# PCB1_new.net
KiCad netlist of a schematic drawn in EAGLE
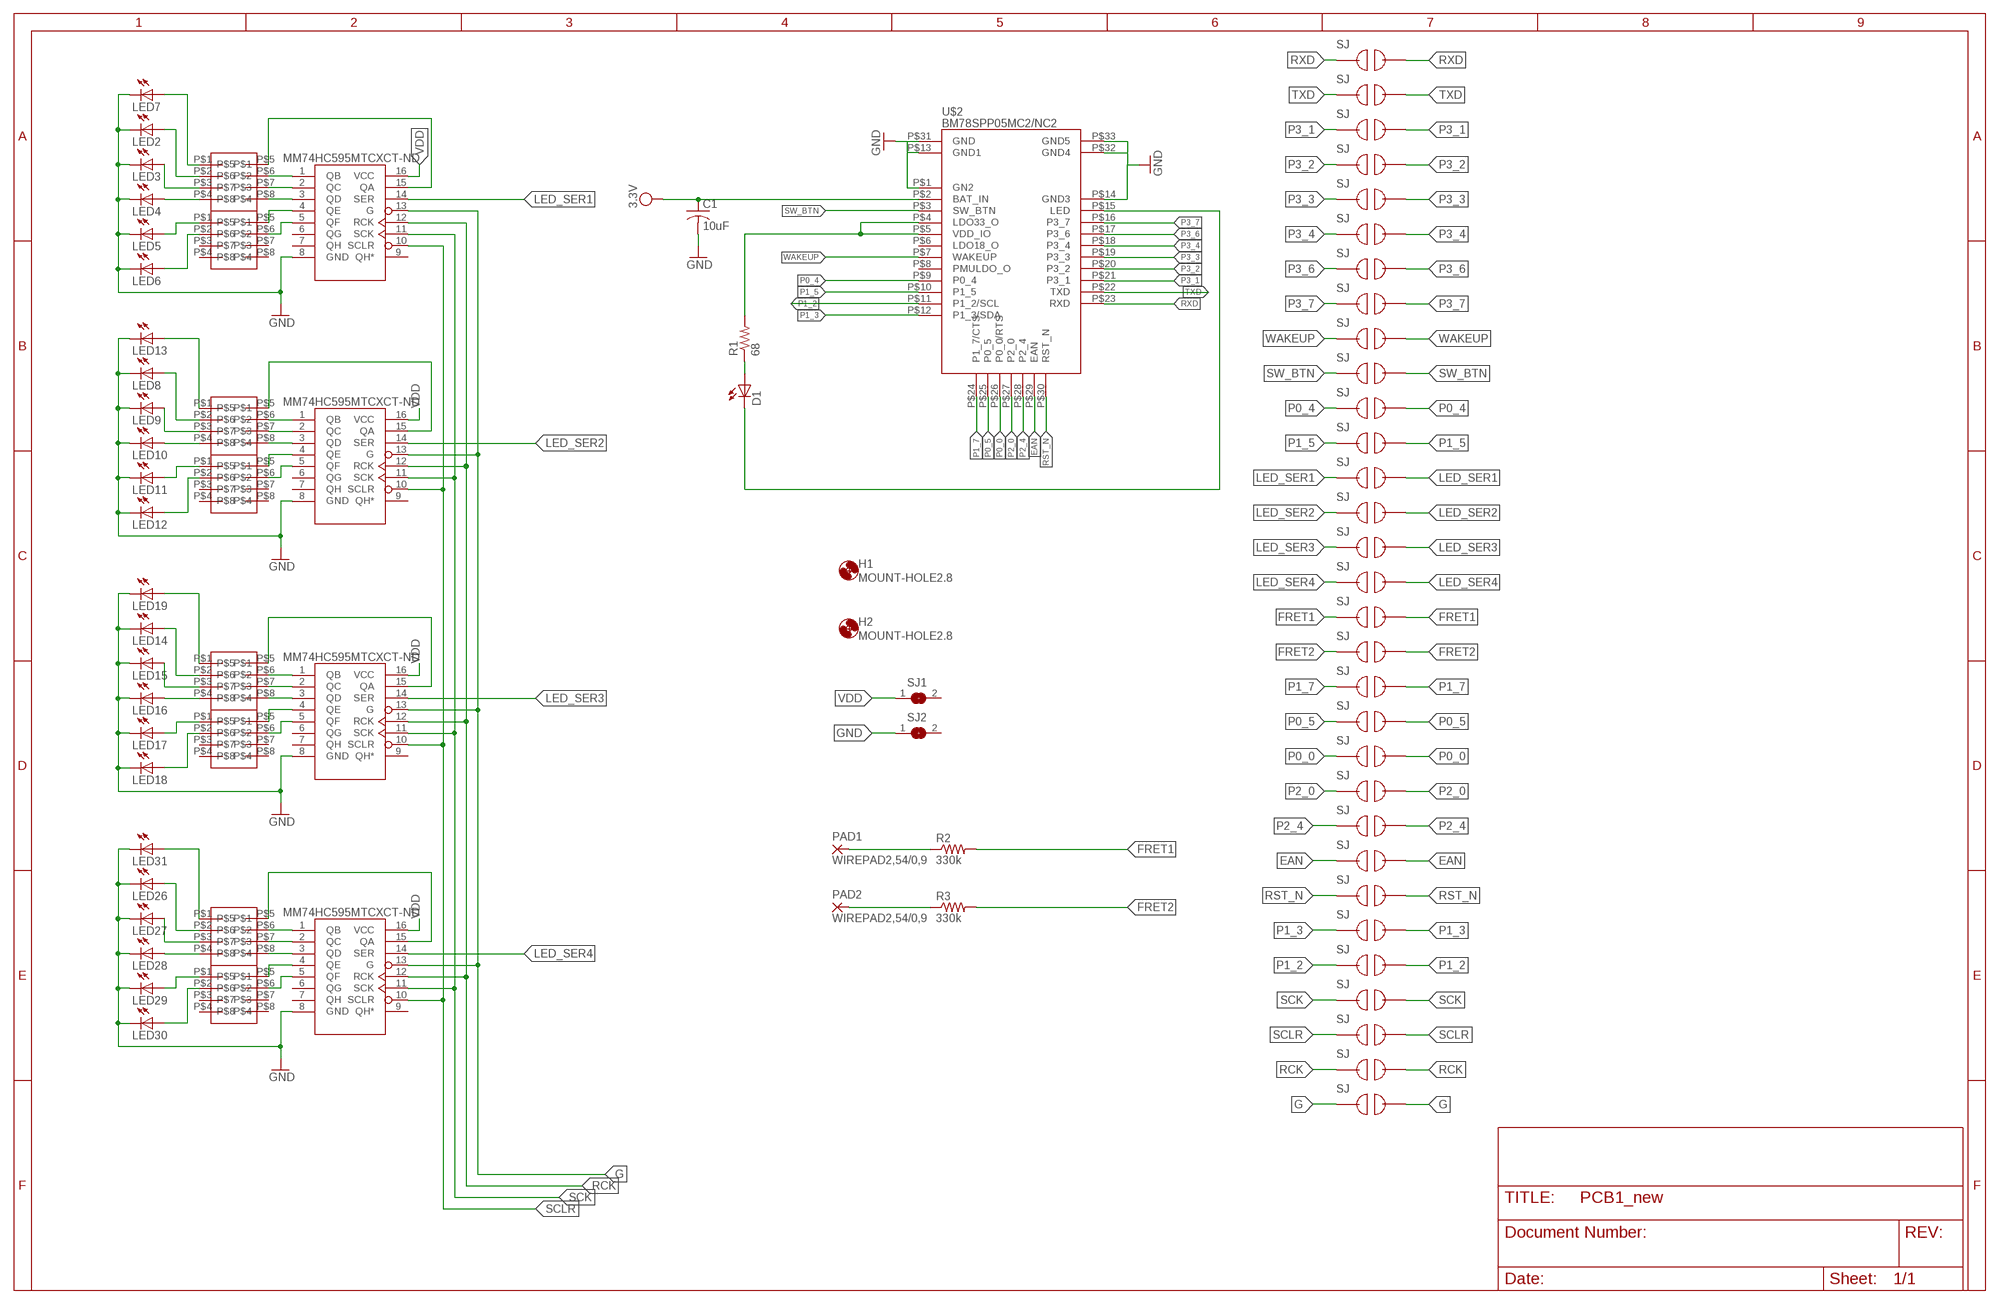
[diagram p0: schematic, sheet 1]

(export (version "E")
  (design (tool "Eeschema 10.0.6"))
  (components
    (comp (ref "C1")
      (value "10uF")
      (footprint "eagle-import:C0805")
      (libsource (lib "eagle-import") (part "C-USC0805"))
    )
    (comp (ref "D1")
      (value "LEDSMT1206")
      (footprint "eagle-import:1206")
      (libsource (lib "eagle-import") (part "LEDSMT1206"))
    )
    (comp (ref "H1")
      (value "MOUNT-HOLE2.8")
      (footprint "eagle-import:2,8")
      (libsource (lib "eagle-import") (part "MOUNT-HOLE2.8"))
    )
    (comp (ref "H2")
      (value "MOUNT-HOLE2.8")
      (footprint "eagle-import:2,8")
      (libsource (lib "eagle-import") (part "MOUNT-HOLE2.8"))
    )
    (comp (ref "LED2")
      (value "LEDSMT1206")
      (footprint "eagle-import:1206")
      (libsource (lib "eagle-import") (part "LEDSMT1206"))
    )
    (comp (ref "LED3")
      (value "LEDSMT1206")
      (footprint "eagle-import:1206")
      (libsource (lib "eagle-import") (part "LEDSMT1206"))
    )
    (comp (ref "LED4")
      (value "LEDSMT1206")
      (footprint "eagle-import:1206")
      (libsource (lib "eagle-import") (part "LEDSMT1206"))
    )
    (comp (ref "LED5")
      (value "LEDSMT1206")
      (footprint "eagle-import:1206")
      (libsource (lib "eagle-import") (part "LEDSMT1206"))
    )
    (comp (ref "LED6")
      (value "LEDSMT1206")
      (footprint "eagle-import:1206")
      (libsource (lib "eagle-import") (part "LEDSMT1206"))
    )
    (comp (ref "LED7")
      (value "LEDSMT1206")
      (footprint "eagle-import:1206")
      (libsource (lib "eagle-import") (part "LEDSMT1206"))
    )
    (comp (ref "LED8")
      (value "LEDSMT1206")
      (footprint "eagle-import:1206")
      (libsource (lib "eagle-import") (part "LEDSMT1206"))
    )
    (comp (ref "LED9")
      (value "LEDSMT1206")
      (footprint "eagle-import:1206")
      (libsource (lib "eagle-import") (part "LEDSMT1206"))
    )
    (comp (ref "LED10")
      (value "LEDSMT1206")
      (footprint "eagle-import:1206")
      (libsource (lib "eagle-import") (part "LEDSMT1206"))
    )
    (comp (ref "LED11")
      (value "LEDSMT1206")
      (footprint "eagle-import:1206")
      (libsource (lib "eagle-import") (part "LEDSMT1206"))
    )
    (comp (ref "LED12")
      (value "LEDSMT1206")
      (footprint "eagle-import:1206")
      (libsource (lib "eagle-import") (part "LEDSMT1206"))
    )
    (comp (ref "LED13")
      (value "LEDSMT1206")
      (footprint "eagle-import:1206")
      (libsource (lib "eagle-import") (part "LEDSMT1206"))
    )
    (comp (ref "LED14")
      (value "LEDSMT1206")
      (footprint "eagle-import:1206")
      (libsource (lib "eagle-import") (part "LEDSMT1206"))
    )
    (comp (ref "LED15")
      (value "LEDSMT1206")
      (footprint "eagle-import:1206")
      (libsource (lib "eagle-import") (part "LEDSMT1206"))
    )
    (comp (ref "LED16")
      (value "LEDSMT1206")
      (footprint "eagle-import:1206")
      (libsource (lib "eagle-import") (part "LEDSMT1206"))
    )
    (comp (ref "LED17")
      (value "LEDSMT1206")
      (footprint "eagle-import:1206")
      (libsource (lib "eagle-import") (part "LEDSMT1206"))
    )
    (comp (ref "LED18")
      (value "LEDSMT1206")
      (footprint "eagle-import:1206")
      (libsource (lib "eagle-import") (part "LEDSMT1206"))
    )
    (comp (ref "LED19")
      (value "LEDSMT1206")
      (footprint "eagle-import:1206")
      (libsource (lib "eagle-import") (part "LEDSMT1206"))
    )
    (comp (ref "LED26")
      (value "LEDSMT1206")
      (footprint "eagle-import:1206")
      (libsource (lib "eagle-import") (part "LEDSMT1206"))
    )
    (comp (ref "LED27")
      (value "LEDSMT1206")
      (footprint "eagle-import:1206")
      (libsource (lib "eagle-import") (part "LEDSMT1206"))
    )
    (comp (ref "LED28")
      (value "LEDSMT1206")
      (footprint "eagle-import:1206")
      (libsource (lib "eagle-import") (part "LEDSMT1206"))
    )
    (comp (ref "LED29")
      (value "LEDSMT1206")
      (footprint "eagle-import:1206")
      (libsource (lib "eagle-import") (part "LEDSMT1206"))
    )
    (comp (ref "LED30")
      (value "LEDSMT1206")
      (footprint "eagle-import:1206")
      (libsource (lib "eagle-import") (part "LEDSMT1206"))
    )
    (comp (ref "LED31")
      (value "LEDSMT1206")
      (footprint "eagle-import:1206")
      (libsource (lib "eagle-import") (part "LEDSMT1206"))
    )
    (comp (ref "PAD1")
      (value "WIREPAD2,54/0,9")
      (footprint "eagle-import:2,54_0,9")
      (libsource (lib "eagle-import") (part "WIREPAD2,54/0,9"))
    )
    (comp (ref "PAD2")
      (value "WIREPAD2,54/0,9")
      (footprint "eagle-import:2,54_0,9")
      (libsource (lib "eagle-import") (part "WIREPAD2,54/0,9"))
    )
    (comp (ref "R1")
      (value "68")
      (footprint "eagle-import:M0805")
      (libsource (lib "eagle-import") (part "R-US_M0805"))
    )
    (comp (ref "R2")
      (value "330k")
      (footprint "eagle-import:R0805")
      (libsource (lib "eagle-import") (part "R-US_R0805"))
    )
    (comp (ref "R3")
      (value "330k")
      (footprint "eagle-import:R0805")
      (libsource (lib "eagle-import") (part "R-US_R0805"))
    )
    (comp (ref "RN1")
      (value "MNR04MRAPJ680")
      (footprint "eagle-import:MNR04")
      (libsource (lib "eagle-import") (part "MNR04MRAPJ680"))
    )
    (comp (ref "RN2")
      (value "MNR04MRAPJ680")
      (footprint "eagle-import:MNR04")
      (libsource (lib "eagle-import") (part "MNR04MRAPJ680"))
    )
    (comp (ref "SJ1")
      (value "SJW")
      (footprint "eagle-import:SJW")
      (libsource (lib "eagle-import") (part "SJW"))
    )
    (comp (ref "SJ2")
      (value "SJW")
      (footprint "eagle-import:SJW")
      (libsource (lib "eagle-import") (part "SJW"))
    )
    (comp (ref "U$1")
      (value "MM74HC595TSSOP-LD16")
      (footprint "eagle-import:MM74HC595MTCXCT-ND")
      (libsource (lib "eagle-import") (part "MM74HC595TSSOP-LD16"))
    )
    (comp (ref "U$2")
      (value "BM78SPP05MC2/NC2")
      (footprint "eagle-import:BM78SPP05MC2_NC2")
      (libsource (lib "eagle-import") (part "BM78SPP05MC2/NC2"))
    )
    (comp (ref "U$3")
      (value "MM74HC595TSSOP-LD16")
      (footprint "eagle-import:MM74HC595MTCXCT-ND")
      (libsource (lib "eagle-import") (part "MM74HC595TSSOP-LD16"))
    )
    (comp (ref "U$4")
      (value "MM74HC595TSSOP-LD16")
      (footprint "eagle-import:MM74HC595MTCXCT-ND")
      (libsource (lib "eagle-import") (part "MM74HC595TSSOP-LD16"))
    )
    (comp (ref "U$5")
      (value "MM74HC595TSSOP-LD16")
      (footprint "eagle-import:MM74HC595MTCXCT-ND")
      (libsource (lib "eagle-import") (part "MM74HC595TSSOP-LD16"))
    )
    (comp (ref "U$6")
      (value "JUMPER")
      (footprint "eagle-import:JUMPER")
      (libsource (lib "eagle-import") (part "JUMPER"))
    )
    (comp (ref "U$7")
      (value "JUMPER")
      (footprint "eagle-import:JUMPER")
      (libsource (lib "eagle-import") (part "JUMPER"))
    )
    (comp (ref "U$8")
      (value "JUMPER")
      (footprint "eagle-import:JUMPER")
      (libsource (lib "eagle-import") (part "JUMPER"))
    )
    (comp (ref "U$9")
      (value "JUMPER")
      (footprint "eagle-import:JUMPER")
      (libsource (lib "eagle-import") (part "JUMPER"))
    )
    (comp (ref "U$10")
      (value "JUMPER")
      (footprint "eagle-import:JUMPER")
      (libsource (lib "eagle-import") (part "JUMPER"))
    )
    (comp (ref "U$11")
      (value "JUMPER")
      (footprint "eagle-import:JUMPER")
      (libsource (lib "eagle-import") (part "JUMPER"))
    )
    (comp (ref "U$12")
      (value "JUMPER")
      (footprint "eagle-import:JUMPER")
      (libsource (lib "eagle-import") (part "JUMPER"))
    )
    (comp (ref "U$13")
      (value "JUMPER")
      (footprint "eagle-import:JUMPER")
      (libsource (lib "eagle-import") (part "JUMPER"))
    )
    (comp (ref "U$14")
      (value "JUMPER")
      (footprint "eagle-import:JUMPER")
      (libsource (lib "eagle-import") (part "JUMPER"))
    )
    (comp (ref "U$15")
      (value "JUMPER")
      (footprint "eagle-import:JUMPER")
      (libsource (lib "eagle-import") (part "JUMPER"))
    )
    (comp (ref "U$16")
      (value "JUMPER")
      (footprint "eagle-import:JUMPER")
      (libsource (lib "eagle-import") (part "JUMPER"))
    )
    (comp (ref "U$17")
      (value "JUMPER")
      (footprint "eagle-import:JUMPER")
      (libsource (lib "eagle-import") (part "JUMPER"))
    )
    (comp (ref "U$18")
      (value "JUMPER")
      (footprint "eagle-import:JUMPER")
      (libsource (lib "eagle-import") (part "JUMPER"))
    )
    (comp (ref "U$19")
      (value "JUMPER")
      (footprint "eagle-import:JUMPER")
      (libsource (lib "eagle-import") (part "JUMPER"))
    )
    (comp (ref "U$20")
      (value "JUMPER")
      (footprint "eagle-import:JUMPER")
      (libsource (lib "eagle-import") (part "JUMPER"))
    )
    (comp (ref "U$21")
      (value "JUMPER")
      (footprint "eagle-import:JUMPER")
      (libsource (lib "eagle-import") (part "JUMPER"))
    )
    (comp (ref "U$22")
      (value "JUMPER")
      (footprint "eagle-import:JUMPER")
      (libsource (lib "eagle-import") (part "JUMPER"))
    )
    (comp (ref "U$23")
      (value "JUMPER")
      (footprint "eagle-import:JUMPER")
      (libsource (lib "eagle-import") (part "JUMPER"))
    )
    (comp (ref "U$24")
      (value "JUMPER")
      (footprint "eagle-import:JUMPER")
      (libsource (lib "eagle-import") (part "JUMPER"))
    )
    (comp (ref "U$25")
      (value "JUMPER")
      (footprint "eagle-import:JUMPER")
      (libsource (lib "eagle-import") (part "JUMPER"))
    )
    (comp (ref "U$26")
      (value "JUMPER")
      (footprint "eagle-import:JUMPER")
      (libsource (lib "eagle-import") (part "JUMPER"))
    )
    (comp (ref "U$27")
      (value "JUMPER")
      (footprint "eagle-import:JUMPER")
      (libsource (lib "eagle-import") (part "JUMPER"))
    )
    (comp (ref "U$28")
      (value "JUMPER")
      (footprint "eagle-import:JUMPER")
      (libsource (lib "eagle-import") (part "JUMPER"))
    )
    (comp (ref "U$29")
      (value "JUMPER")
      (footprint "eagle-import:JUMPER")
      (libsource (lib "eagle-import") (part "JUMPER"))
    )
    (comp (ref "U$30")
      (value "JUMPER")
      (footprint "eagle-import:JUMPER")
      (libsource (lib "eagle-import") (part "JUMPER"))
    )
    (comp (ref "U$31")
      (value "JUMPER")
      (footprint "eagle-import:JUMPER")
      (libsource (lib "eagle-import") (part "JUMPER"))
    )
    (comp (ref "U$32")
      (value "JUMPER")
      (footprint "eagle-import:JUMPER")
      (libsource (lib "eagle-import") (part "JUMPER"))
    )
    (comp (ref "U$33")
      (value "JUMPER")
      (footprint "eagle-import:JUMPER")
      (libsource (lib "eagle-import") (part "JUMPER"))
    )
    (comp (ref "U$34")
      (value "JUMPER")
      (footprint "eagle-import:JUMPER")
      (libsource (lib "eagle-import") (part "JUMPER"))
    )
    (comp (ref "U$35")
      (value "JUMPER")
      (footprint "eagle-import:JUMPER")
      (libsource (lib "eagle-import") (part "JUMPER"))
    )
    (comp (ref "U$36")
      (value "JUMPER")
      (footprint "eagle-import:JUMPER")
      (libsource (lib "eagle-import") (part "JUMPER"))
    )
    (comp (ref "U$39")
      (value "MNR04MRAPJ680")
      (footprint "eagle-import:MNR04")
      (libsource (lib "eagle-import") (part "MNR04MRAPJ680"))
    )
    (comp (ref "U$40")
      (value "MNR04MRAPJ680")
      (footprint "eagle-import:MNR04")
      (libsource (lib "eagle-import") (part "MNR04MRAPJ680"))
    )
    (comp (ref "U$41")
      (value "MNR04MRAPJ680")
      (footprint "eagle-import:MNR04")
      (libsource (lib "eagle-import") (part "MNR04MRAPJ680"))
    )
    (comp (ref "U$42")
      (value "MNR04MRAPJ680")
      (footprint "eagle-import:MNR04")
      (libsource (lib "eagle-import") (part "MNR04MRAPJ680"))
    )
    (comp (ref "U$43")
      (value "MNR04MRAPJ680")
      (footprint "eagle-import:MNR04")
      (libsource (lib "eagle-import") (part "MNR04MRAPJ680"))
    )
    (comp (ref "U$44")
      (value "MNR04MRAPJ680")
      (footprint "eagle-import:MNR04")
      (libsource (lib "eagle-import") (part "MNR04MRAPJ680"))
    )
  )
  (nets
    (net (code "1") (name "EAN") (class "Default")
      (node (ref "U$2") (pin "P$29") (pinfunction "EAN_P$29") (pintype "bidirectional"))
      (node (ref "U$26") (pin "P$1") (pinfunction "P$1_P$1") (pintype "bidirectional"))
      (node (ref "U$26") (pin "P$2") (pinfunction "P$2_P$2") (pintype "bidirectional"))
    )
    (net (code "2") (name "FRET1") (class "Default")
      (node (ref "R2") (pin "2") (pinfunction "2_2") (pintype "passive"))
      (node (ref "U$19") (pin "P$1") (pinfunction "P$1_P$1") (pintype "bidirectional"))
      (node (ref "U$19") (pin "P$2") (pinfunction "P$2_P$2") (pintype "bidirectional"))
    )
    (net (code "3") (name "FRET2") (class "Default")
      (node (ref "R3") (pin "2") (pinfunction "2_2") (pintype "passive"))
      (node (ref "U$20") (pin "P$1") (pinfunction "P$1_P$1") (pintype "bidirectional"))
      (node (ref "U$20") (pin "P$2") (pinfunction "P$2_P$2") (pintype "bidirectional"))
    )
    (net (code "4") (name "G") (class "Default")
      (node (ref "U$1") (pin "13") (pinfunction "G_13") (pintype "bidirectional"))
      (node (ref "U$3") (pin "13") (pinfunction "G_13") (pintype "bidirectional"))
      (node (ref "U$30") (pin "P$1") (pinfunction "P$1_P$1") (pintype "bidirectional"))
      (node (ref "U$30") (pin "P$2") (pinfunction "P$2_P$2") (pintype "bidirectional"))
      (node (ref "U$4") (pin "13") (pinfunction "G_13") (pintype "bidirectional"))
      (node (ref "U$5") (pin "13") (pinfunction "G_13") (pintype "bidirectional"))
    )
    (net (code "5") (name "GND") (class "Default")
      (node (ref "C1") (pin "2") (pinfunction "2_2") (pintype "passive"))
      (node (ref "LED10") (pin "C") (pinfunction "C_C") (pintype "passive"))
      (node (ref "LED11") (pin "C") (pinfunction "C_C") (pintype "passive"))
      (node (ref "LED12") (pin "C") (pinfunction "C_C") (pintype "passive"))
      (node (ref "LED13") (pin "C") (pinfunction "C_C") (pintype "passive"))
      (node (ref "LED14") (pin "C") (pinfunction "C_C") (pintype "passive"))
      (node (ref "LED15") (pin "C") (pinfunction "C_C") (pintype "passive"))
      (node (ref "LED16") (pin "C") (pinfunction "C_C") (pintype "passive"))
      (node (ref "LED17") (pin "C") (pinfunction "C_C") (pintype "passive"))
      (node (ref "LED18") (pin "C") (pinfunction "C_C") (pintype "passive"))
      (node (ref "LED19") (pin "C") (pinfunction "C_C") (pintype "passive"))
      (node (ref "LED2") (pin "C") (pinfunction "C_C") (pintype "passive"))
      (node (ref "LED26") (pin "C") (pinfunction "C_C") (pintype "passive"))
      (node (ref "LED27") (pin "C") (pinfunction "C_C") (pintype "passive"))
      (node (ref "LED28") (pin "C") (pinfunction "C_C") (pintype "passive"))
      (node (ref "LED29") (pin "C") (pinfunction "C_C") (pintype "passive"))
      (node (ref "LED3") (pin "C") (pinfunction "C_C") (pintype "passive"))
      (node (ref "LED30") (pin "C") (pinfunction "C_C") (pintype "passive"))
      (node (ref "LED31") (pin "C") (pinfunction "C_C") (pintype "passive"))
      (node (ref "LED4") (pin "C") (pinfunction "C_C") (pintype "passive"))
      (node (ref "LED5") (pin "C") (pinfunction "C_C") (pintype "passive"))
      (node (ref "LED6") (pin "C") (pinfunction "C_C") (pintype "passive"))
      (node (ref "LED7") (pin "C") (pinfunction "C_C") (pintype "passive"))
      (node (ref "LED8") (pin "C") (pinfunction "C_C") (pintype "passive"))
      (node (ref "LED9") (pin "C") (pinfunction "C_C") (pintype "passive"))
      (node (ref "SJ2") (pin "1") (pinfunction "1_1") (pintype "passive"))
      (node (ref "U$1") (pin "8") (pinfunction "GND_8") (pintype "bidirectional"))
      (node (ref "U$2") (pin "P$1") (pinfunction "GN2_P$1") (pintype "bidirectional"))
      (node (ref "U$2") (pin "P$13") (pinfunction "GND1_P$13") (pintype "bidirectional"))
      (node (ref "U$2") (pin "P$14") (pinfunction "GND3_P$14") (pintype "bidirectional"))
      (node (ref "U$2") (pin "P$31") (pinfunction "GND_P$31") (pintype "bidirectional"))
      (node (ref "U$2") (pin "P$32") (pinfunction "GND4_P$32") (pintype "bidirectional"))
      (node (ref "U$2") (pin "P$33") (pinfunction "GND5_P$33") (pintype "bidirectional"))
      (node (ref "U$3") (pin "8") (pinfunction "GND_8") (pintype "bidirectional"))
      (node (ref "U$4") (pin "8") (pinfunction "GND_8") (pintype "bidirectional"))
      (node (ref "U$5") (pin "8") (pinfunction "GND_8") (pintype "bidirectional"))
    )
    (net (code "6") (name "LED_SER1") (class "Default")
      (node (ref "U$15") (pin "P$1") (pinfunction "P$1_P$1") (pintype "bidirectional"))
      (node (ref "U$15") (pin "P$2") (pinfunction "P$2_P$2") (pintype "bidirectional"))
      (node (ref "U$4") (pin "14") (pinfunction "SER_14") (pintype "bidirectional"))
    )
    (net (code "7") (name "LED_SER2") (class "Default")
      (node (ref "U$1") (pin "14") (pinfunction "SER_14") (pintype "bidirectional"))
      (node (ref "U$16") (pin "P$1") (pinfunction "P$1_P$1") (pintype "bidirectional"))
      (node (ref "U$16") (pin "P$2") (pinfunction "P$2_P$2") (pintype "bidirectional"))
    )
    (net (code "8") (name "LED_SER3") (class "Default")
      (node (ref "U$17") (pin "P$1") (pinfunction "P$1_P$1") (pintype "bidirectional"))
      (node (ref "U$17") (pin "P$2") (pinfunction "P$2_P$2") (pintype "bidirectional"))
      (node (ref "U$3") (pin "14") (pinfunction "SER_14") (pintype "bidirectional"))
    )
    (net (code "9") (name "LED_SER4") (class "Default")
      (node (ref "U$18") (pin "P$1") (pinfunction "P$1_P$1") (pintype "bidirectional"))
      (node (ref "U$18") (pin "P$2") (pinfunction "P$2_P$2") (pintype "bidirectional"))
      (node (ref "U$5") (pin "14") (pinfunction "SER_14") (pintype "bidirectional"))
    )
    (net (code "10") (name "Net-(D1-PadA)") (class "Default")
      (node (ref "D1") (pin "A") (pinfunction "A_A") (pintype "passive"))
      (node (ref "R1") (pin "1") (pinfunction "1_1") (pintype "passive"))
    )
    (net (code "11") (name "Net-(LED2-PadA)") (class "Default")
      (node (ref "LED2") (pin "A") (pinfunction "A_A") (pintype "passive"))
      (node (ref "RN1") (pin "P$2") (pinfunction "P$2_P$2") (pintype "bidirectional"))
    )
    (net (code "12") (name "Net-(LED3-PadA)") (class "Default")
      (node (ref "LED3") (pin "A") (pinfunction "A_A") (pintype "passive"))
      (node (ref "RN1") (pin "P$3") (pinfunction "P$3_P$3") (pintype "bidirectional"))
    )
    (net (code "13") (name "Net-(LED4-PadA)") (class "Default")
      (node (ref "LED4") (pin "A") (pinfunction "A_A") (pintype "passive"))
      (node (ref "RN1") (pin "P$4") (pinfunction "P$4_P$4") (pintype "bidirectional"))
    )
    (net (code "14") (name "Net-(LED5-PadA)") (class "Default")
      (node (ref "LED5") (pin "A") (pinfunction "A_A") (pintype "passive"))
      (node (ref "RN2") (pin "P$1") (pinfunction "P$1_P$1") (pintype "bidirectional"))
    )
    (net (code "15") (name "Net-(LED6-PadA)") (class "Default")
      (node (ref "LED6") (pin "A") (pinfunction "A_A") (pintype "passive"))
      (node (ref "RN2") (pin "P$2") (pinfunction "P$2_P$2") (pintype "bidirectional"))
    )
    (net (code "16") (name "Net-(LED7-PadA)") (class "Default")
      (node (ref "LED7") (pin "A") (pinfunction "A_A") (pintype "passive"))
      (node (ref "RN1") (pin "P$1") (pinfunction "P$1_P$1") (pintype "bidirectional"))
    )
    (net (code "17") (name "Net-(LED8-PadA)") (class "Default")
      (node (ref "LED8") (pin "A") (pinfunction "A_A") (pintype "passive"))
      (node (ref "U$39") (pin "P$2") (pinfunction "P$2_P$2") (pintype "bidirectional"))
    )
    (net (code "18") (name "Net-(LED9-PadA)") (class "Default")
      (node (ref "LED9") (pin "A") (pinfunction "A_A") (pintype "passive"))
      (node (ref "U$39") (pin "P$3") (pinfunction "P$3_P$3") (pintype "bidirectional"))
    )
    (net (code "19") (name "Net-(LED10-PadA)") (class "Default")
      (node (ref "LED10") (pin "A") (pinfunction "A_A") (pintype "passive"))
      (node (ref "U$39") (pin "P$4") (pinfunction "P$4_P$4") (pintype "bidirectional"))
    )
    (net (code "20") (name "Net-(LED11-PadA)") (class "Default")
      (node (ref "LED11") (pin "A") (pinfunction "A_A") (pintype "passive"))
      (node (ref "U$40") (pin "P$1") (pinfunction "P$1_P$1") (pintype "bidirectional"))
    )
    (net (code "21") (name "Net-(LED12-PadA)") (class "Default")
      (node (ref "LED12") (pin "A") (pinfunction "A_A") (pintype "passive"))
      (node (ref "U$40") (pin "P$2") (pinfunction "P$2_P$2") (pintype "bidirectional"))
    )
    (net (code "22") (name "Net-(LED13-PadA)") (class "Default")
      (node (ref "LED13") (pin "A") (pinfunction "A_A") (pintype "passive"))
      (node (ref "U$39") (pin "P$1") (pinfunction "P$1_P$1") (pintype "bidirectional"))
    )
    (net (code "23") (name "Net-(LED14-PadA)") (class "Default")
      (node (ref "LED14") (pin "A") (pinfunction "A_A") (pintype "passive"))
      (node (ref "U$41") (pin "P$2") (pinfunction "P$2_P$2") (pintype "bidirectional"))
    )
    (net (code "24") (name "Net-(LED15-PadA)") (class "Default")
      (node (ref "LED15") (pin "A") (pinfunction "A_A") (pintype "passive"))
      (node (ref "U$41") (pin "P$3") (pinfunction "P$3_P$3") (pintype "bidirectional"))
    )
    (net (code "25") (name "Net-(LED16-PadA)") (class "Default")
      (node (ref "LED16") (pin "A") (pinfunction "A_A") (pintype "passive"))
      (node (ref "U$41") (pin "P$4") (pinfunction "P$4_P$4") (pintype "bidirectional"))
    )
    (net (code "26") (name "Net-(LED17-PadA)") (class "Default")
      (node (ref "LED17") (pin "A") (pinfunction "A_A") (pintype "passive"))
      (node (ref "U$42") (pin "P$1") (pinfunction "P$1_P$1") (pintype "bidirectional"))
    )
    (net (code "27") (name "Net-(LED18-PadA)") (class "Default")
      (node (ref "LED18") (pin "A") (pinfunction "A_A") (pintype "passive"))
      (node (ref "U$42") (pin "P$2") (pinfunction "P$2_P$2") (pintype "bidirectional"))
    )
    (net (code "28") (name "Net-(LED19-PadA)") (class "Default")
      (node (ref "LED19") (pin "A") (pinfunction "A_A") (pintype "passive"))
      (node (ref "U$41") (pin "P$1") (pinfunction "P$1_P$1") (pintype "bidirectional"))
    )
    (net (code "29") (name "Net-(LED26-PadA)") (class "Default")
      (node (ref "LED26") (pin "A") (pinfunction "A_A") (pintype "passive"))
      (node (ref "U$43") (pin "P$2") (pinfunction "P$2_P$2") (pintype "bidirectional"))
    )
    (net (code "30") (name "Net-(LED27-PadA)") (class "Default")
      (node (ref "LED27") (pin "A") (pinfunction "A_A") (pintype "passive"))
      (node (ref "U$43") (pin "P$3") (pinfunction "P$3_P$3") (pintype "bidirectional"))
    )
    (net (code "31") (name "Net-(LED28-PadA)") (class "Default")
      (node (ref "LED28") (pin "A") (pinfunction "A_A") (pintype "passive"))
      (node (ref "U$43") (pin "P$4") (pinfunction "P$4_P$4") (pintype "bidirectional"))
    )
    (net (code "32") (name "Net-(LED29-PadA)") (class "Default")
      (node (ref "LED29") (pin "A") (pinfunction "A_A") (pintype "passive"))
      (node (ref "U$44") (pin "P$1") (pinfunction "P$1_P$1") (pintype "bidirectional"))
    )
    (net (code "33") (name "Net-(LED30-PadA)") (class "Default")
      (node (ref "LED30") (pin "A") (pinfunction "A_A") (pintype "passive"))
      (node (ref "U$44") (pin "P$2") (pinfunction "P$2_P$2") (pintype "bidirectional"))
    )
    (net (code "34") (name "Net-(LED31-PadA)") (class "Default")
      (node (ref "LED31") (pin "A") (pinfunction "A_A") (pintype "passive"))
      (node (ref "U$43") (pin "P$1") (pinfunction "P$1_P$1") (pintype "bidirectional"))
    )
    (net (code "35") (name "Net-(PAD1-P)") (class "Default")
      (node (ref "PAD1") (pin "1") (pinfunction "P_1") (pintype "passive"))
      (node (ref "R2") (pin "1") (pinfunction "1_1") (pintype "passive"))
    )
    (net (code "36") (name "Net-(PAD2-P)") (class "Default")
      (node (ref "PAD2") (pin "1") (pinfunction "P_1") (pintype "passive"))
      (node (ref "R3") (pin "1") (pinfunction "1_1") (pintype "passive"))
    )
    (net (code "37") (name "Net-(U$1-QA)") (class "Default")
      (node (ref "U$1") (pin "15") (pinfunction "QA_15") (pintype "bidirectional"))
      (node (ref "U$39") (pin "P$5") (pinfunction "P$5_P$5") (pintype "bidirectional"))
    )
    (net (code "38") (name "Net-(U$1-QB)") (class "Default")
      (node (ref "U$1") (pin "1") (pinfunction "QB_1") (pintype "bidirectional"))
      (node (ref "U$39") (pin "P$6") (pinfunction "P$6_P$6") (pintype "bidirectional"))
    )
    (net (code "39") (name "Net-(U$1-QC)") (class "Default")
      (node (ref "U$1") (pin "2") (pinfunction "QC_2") (pintype "bidirectional"))
      (node (ref "U$39") (pin "P$7") (pinfunction "P$7_P$7") (pintype "bidirectional"))
    )
    (net (code "40") (name "Net-(U$1-QD)") (class "Default")
      (node (ref "U$1") (pin "3") (pinfunction "QD_3") (pintype "bidirectional"))
      (node (ref "U$39") (pin "P$8") (pinfunction "P$8_P$8") (pintype "bidirectional"))
    )
    (net (code "41") (name "Net-(U$1-QE)") (class "Default")
      (node (ref "U$1") (pin "4") (pinfunction "QE_4") (pintype "bidirectional"))
      (node (ref "U$40") (pin "P$5") (pinfunction "P$5_P$5") (pintype "bidirectional"))
    )
    (net (code "42") (name "Net-(U$1-QF)") (class "Default")
      (node (ref "U$1") (pin "5") (pinfunction "QF_5") (pintype "bidirectional"))
      (node (ref "U$40") (pin "P$6") (pinfunction "P$6_P$6") (pintype "bidirectional"))
    )
    (net (code "43") (name "Net-(U$2-LDO33_O)") (class "Default")
      (node (ref "R1") (pin "2") (pinfunction "2_2") (pintype "passive"))
      (node (ref "U$2") (pin "P$4") (pinfunction "LDO33_O_P$4") (pintype "bidirectional"))
      (node (ref "U$2") (pin "P$5") (pinfunction "VDD_IO_P$5") (pintype "bidirectional"))
    )
    (net (code "44") (name "Net-(U$2-LED)") (class "Default")
      (node (ref "D1") (pin "C") (pinfunction "C_C") (pintype "passive"))
      (node (ref "U$2") (pin "P$15") (pinfunction "LED_P$15") (pintype "bidirectional"))
    )
    (net (code "45") (name "Net-(U$3-QA)") (class "Default")
      (node (ref "U$3") (pin "15") (pinfunction "QA_15") (pintype "bidirectional"))
      (node (ref "U$41") (pin "P$5") (pinfunction "P$5_P$5") (pintype "bidirectional"))
    )
    (net (code "46") (name "Net-(U$3-QB)") (class "Default")
      (node (ref "U$3") (pin "1") (pinfunction "QB_1") (pintype "bidirectional"))
      (node (ref "U$41") (pin "P$6") (pinfunction "P$6_P$6") (pintype "bidirectional"))
    )
    (net (code "47") (name "Net-(U$3-QC)") (class "Default")
      (node (ref "U$3") (pin "2") (pinfunction "QC_2") (pintype "bidirectional"))
      (node (ref "U$41") (pin "P$7") (pinfunction "P$7_P$7") (pintype "bidirectional"))
    )
    (net (code "48") (name "Net-(U$3-QD)") (class "Default")
      (node (ref "U$3") (pin "3") (pinfunction "QD_3") (pintype "bidirectional"))
      (node (ref "U$41") (pin "P$8") (pinfunction "P$8_P$8") (pintype "bidirectional"))
    )
    (net (code "49") (name "Net-(U$3-QE)") (class "Default")
      (node (ref "U$3") (pin "4") (pinfunction "QE_4") (pintype "bidirectional"))
      (node (ref "U$42") (pin "P$5") (pinfunction "P$5_P$5") (pintype "bidirectional"))
    )
    (net (code "50") (name "Net-(U$3-QF)") (class "Default")
      (node (ref "U$3") (pin "5") (pinfunction "QF_5") (pintype "bidirectional"))
      (node (ref "U$42") (pin "P$6") (pinfunction "P$6_P$6") (pintype "bidirectional"))
    )
    (net (code "51") (name "Net-(U$4-QA)") (class "Default")
      (node (ref "RN1") (pin "P$5") (pinfunction "P$5_P$5") (pintype "bidirectional"))
      (node (ref "U$4") (pin "15") (pinfunction "QA_15") (pintype "bidirectional"))
    )
    (net (code "52") (name "Net-(U$4-QB)") (class "Default")
      (node (ref "RN1") (pin "P$6") (pinfunction "P$6_P$6") (pintype "bidirectional"))
      (node (ref "U$4") (pin "1") (pinfunction "QB_1") (pintype "bidirectional"))
    )
    (net (code "53") (name "Net-(U$4-QC)") (class "Default")
      (node (ref "RN1") (pin "P$7") (pinfunction "P$7_P$7") (pintype "bidirectional"))
      (node (ref "U$4") (pin "2") (pinfunction "QC_2") (pintype "bidirectional"))
    )
    (net (code "54") (name "Net-(U$4-QD)") (class "Default")
      (node (ref "RN1") (pin "P$8") (pinfunction "P$8_P$8") (pintype "bidirectional"))
      (node (ref "U$4") (pin "3") (pinfunction "QD_3") (pintype "bidirectional"))
    )
    (net (code "55") (name "Net-(U$4-QE)") (class "Default")
      (node (ref "RN2") (pin "P$5") (pinfunction "P$5_P$5") (pintype "bidirectional"))
      (node (ref "U$4") (pin "4") (pinfunction "QE_4") (pintype "bidirectional"))
    )
    (net (code "56") (name "Net-(U$4-QF)") (class "Default")
      (node (ref "RN2") (pin "P$6") (pinfunction "P$6_P$6") (pintype "bidirectional"))
      (node (ref "U$4") (pin "5") (pinfunction "QF_5") (pintype "bidirectional"))
    )
    (net (code "57") (name "Net-(U$5-QA)") (class "Default")
      (node (ref "U$43") (pin "P$5") (pinfunction "P$5_P$5") (pintype "bidirectional"))
      (node (ref "U$5") (pin "15") (pinfunction "QA_15") (pintype "bidirectional"))
    )
    (net (code "58") (name "Net-(U$5-QB)") (class "Default")
      (node (ref "U$43") (pin "P$6") (pinfunction "P$6_P$6") (pintype "bidirectional"))
      (node (ref "U$5") (pin "1") (pinfunction "QB_1") (pintype "bidirectional"))
    )
    (net (code "59") (name "Net-(U$5-QC)") (class "Default")
      (node (ref "U$43") (pin "P$7") (pinfunction "P$7_P$7") (pintype "bidirectional"))
      (node (ref "U$5") (pin "2") (pinfunction "QC_2") (pintype "bidirectional"))
    )
    (net (code "60") (name "Net-(U$5-QD)") (class "Default")
      (node (ref "U$43") (pin "P$8") (pinfunction "P$8_P$8") (pintype "bidirectional"))
      (node (ref "U$5") (pin "3") (pinfunction "QD_3") (pintype "bidirectional"))
    )
    (net (code "61") (name "Net-(U$5-QE)") (class "Default")
      (node (ref "U$44") (pin "P$5") (pinfunction "P$5_P$5") (pintype "bidirectional"))
      (node (ref "U$5") (pin "4") (pinfunction "QE_4") (pintype "bidirectional"))
    )
    (net (code "62") (name "Net-(U$5-QF)") (class "Default")
      (node (ref "U$44") (pin "P$6") (pinfunction "P$6_P$6") (pintype "bidirectional"))
      (node (ref "U$5") (pin "5") (pinfunction "QF_5") (pintype "bidirectional"))
    )
    (net (code "63") (name "P0_0") (class "Default")
      (node (ref "U$2") (pin "P$26") (pinfunction "P0_0/RTS_P$26") (pintype "bidirectional"))
      (node (ref "U$23") (pin "P$1") (pinfunction "P$1_P$1") (pintype "bidirectional"))
      (node (ref "U$23") (pin "P$2") (pinfunction "P$2_P$2") (pintype "bidirectional"))
    )
    (net (code "64") (name "P0_4") (class "Default")
      (node (ref "U$13") (pin "P$1") (pinfunction "P$1_P$1") (pintype "bidirectional"))
      (node (ref "U$13") (pin "P$2") (pinfunction "P$2_P$2") (pintype "bidirectional"))
      (node (ref "U$2") (pin "P$9") (pinfunction "P0_4_P$9") (pintype "bidirectional"))
    )
    (net (code "65") (name "P0_5") (class "Default")
      (node (ref "U$2") (pin "P$25") (pinfunction "P0_5_P$25") (pintype "bidirectional"))
      (node (ref "U$22") (pin "P$1") (pinfunction "P$1_P$1") (pintype "bidirectional"))
      (node (ref "U$22") (pin "P$2") (pinfunction "P$2_P$2") (pintype "bidirectional"))
    )
    (net (code "66") (name "P1_2") (class "Default")
      (node (ref "U$2") (pin "P$11") (pinfunction "P1_2/SCL_P$11") (pintype "bidirectional"))
      (node (ref "U$29") (pin "P$1") (pinfunction "P$1_P$1") (pintype "bidirectional"))
      (node (ref "U$29") (pin "P$2") (pinfunction "P$2_P$2") (pintype "bidirectional"))
    )
    (net (code "67") (name "P1_3") (class "Default")
      (node (ref "U$2") (pin "P$12") (pinfunction "P1_3/SDA_P$12") (pintype "bidirectional"))
      (node (ref "U$28") (pin "P$1") (pinfunction "P$1_P$1") (pintype "bidirectional"))
      (node (ref "U$28") (pin "P$2") (pinfunction "P$2_P$2") (pintype "bidirectional"))
    )
    (net (code "68") (name "P1_5") (class "Default")
      (node (ref "U$14") (pin "P$1") (pinfunction "P$1_P$1") (pintype "bidirectional"))
      (node (ref "U$14") (pin "P$2") (pinfunction "P$2_P$2") (pintype "bidirectional"))
      (node (ref "U$2") (pin "P$10") (pinfunction "P1_5_P$10") (pintype "bidirectional"))
    )
    (net (code "69") (name "P1_7") (class "Default")
      (node (ref "U$2") (pin "P$24") (pinfunction "P1_7/CTS_P$24") (pintype "bidirectional"))
      (node (ref "U$21") (pin "P$1") (pinfunction "P$1_P$1") (pintype "bidirectional"))
      (node (ref "U$21") (pin "P$2") (pinfunction "P$2_P$2") (pintype "bidirectional"))
    )
    (net (code "70") (name "P2_0") (class "Default")
      (node (ref "U$2") (pin "P$27") (pinfunction "P2_0_P$27") (pintype "bidirectional"))
      (node (ref "U$24") (pin "P$1") (pinfunction "P$1_P$1") (pintype "bidirectional"))
      (node (ref "U$24") (pin "P$2") (pinfunction "P$2_P$2") (pintype "bidirectional"))
    )
    (net (code "71") (name "P2_4") (class "Default")
      (node (ref "U$2") (pin "P$28") (pinfunction "P2_4_P$28") (pintype "bidirectional"))
      (node (ref "U$25") (pin "P$1") (pinfunction "P$1_P$1") (pintype "bidirectional"))
      (node (ref "U$25") (pin "P$2") (pinfunction "P$2_P$2") (pintype "bidirectional"))
    )
    (net (code "72") (name "P3_1") (class "Default")
      (node (ref "U$2") (pin "P$21") (pinfunction "P3_1_P$21") (pintype "bidirectional"))
      (node (ref "U$33") (pin "P$1") (pinfunction "P$1_P$1") (pintype "bidirectional"))
      (node (ref "U$33") (pin "P$2") (pinfunction "P$2_P$2") (pintype "bidirectional"))
    )
    (net (code "73") (name "P3_2") (class "Default")
      (node (ref "U$2") (pin "P$20") (pinfunction "P3_2_P$20") (pintype "bidirectional"))
      (node (ref "U$6") (pin "P$1") (pinfunction "P$1_P$1") (pintype "bidirectional"))
      (node (ref "U$6") (pin "P$2") (pinfunction "P$2_P$2") (pintype "bidirectional"))
    )
    (net (code "74") (name "P3_3") (class "Default")
      (node (ref "U$2") (pin "P$19") (pinfunction "P3_3_P$19") (pintype "bidirectional"))
      (node (ref "U$7") (pin "P$1") (pinfunction "P$1_P$1") (pintype "bidirectional"))
      (node (ref "U$7") (pin "P$2") (pinfunction "P$2_P$2") (pintype "bidirectional"))
    )
    (net (code "75") (name "P3_4") (class "Default")
      (node (ref "U$2") (pin "P$18") (pinfunction "P3_4_P$18") (pintype "bidirectional"))
      (node (ref "U$8") (pin "P$1") (pinfunction "P$1_P$1") (pintype "bidirectional"))
      (node (ref "U$8") (pin "P$2") (pinfunction "P$2_P$2") (pintype "bidirectional"))
    )
    (net (code "76") (name "P3_6") (class "Default")
      (node (ref "U$2") (pin "P$17") (pinfunction "P3_6_P$17") (pintype "bidirectional"))
      (node (ref "U$9") (pin "P$1") (pinfunction "P$1_P$1") (pintype "bidirectional"))
      (node (ref "U$9") (pin "P$2") (pinfunction "P$2_P$2") (pintype "bidirectional"))
    )
    (net (code "77") (name "P3_7") (class "Default")
      (node (ref "U$10") (pin "P$1") (pinfunction "P$1_P$1") (pintype "bidirectional"))
      (node (ref "U$10") (pin "P$2") (pinfunction "P$2_P$2") (pintype "bidirectional"))
      (node (ref "U$2") (pin "P$16") (pinfunction "P3_7_P$16") (pintype "bidirectional"))
    )
    (net (code "78") (name "RCK") (class "Default")
      (node (ref "U$1") (pin "12") (pinfunction "RCK_12") (pintype "bidirectional"))
      (node (ref "U$3") (pin "12") (pinfunction "RCK_12") (pintype "bidirectional"))
      (node (ref "U$31") (pin "P$1") (pinfunction "P$1_P$1") (pintype "bidirectional"))
      (node (ref "U$31") (pin "P$2") (pinfunction "P$2_P$2") (pintype "bidirectional"))
      (node (ref "U$4") (pin "12") (pinfunction "RCK_12") (pintype "bidirectional"))
      (node (ref "U$5") (pin "12") (pinfunction "RCK_12") (pintype "bidirectional"))
    )
    (net (code "79") (name "RST_N") (class "Default")
      (node (ref "U$2") (pin "P$30") (pinfunction "RST_N_P$30") (pintype "bidirectional"))
      (node (ref "U$27") (pin "P$1") (pinfunction "P$1_P$1") (pintype "bidirectional"))
      (node (ref "U$27") (pin "P$2") (pinfunction "P$2_P$2") (pintype "bidirectional"))
    )
    (net (code "80") (name "RXD") (class "Default")
      (node (ref "U$2") (pin "P$23") (pinfunction "RXD_P$23") (pintype "bidirectional"))
      (node (ref "U$35") (pin "P$1") (pinfunction "P$1_P$1") (pintype "bidirectional"))
      (node (ref "U$35") (pin "P$2") (pinfunction "P$2_P$2") (pintype "bidirectional"))
    )
    (net (code "81") (name "SCK") (class "Default")
      (node (ref "U$1") (pin "11") (pinfunction "SCK_11") (pintype "bidirectional"))
      (node (ref "U$3") (pin "11") (pinfunction "SCK_11") (pintype "bidirectional"))
      (node (ref "U$32") (pin "P$1") (pinfunction "P$1_P$1") (pintype "bidirectional"))
      (node (ref "U$32") (pin "P$2") (pinfunction "P$2_P$2") (pintype "bidirectional"))
      (node (ref "U$4") (pin "11") (pinfunction "SCK_11") (pintype "bidirectional"))
      (node (ref "U$5") (pin "11") (pinfunction "SCK_11") (pintype "bidirectional"))
    )
    (net (code "82") (name "SCLR") (class "Default")
      (node (ref "U$1") (pin "10") (pinfunction "SCLR_10") (pintype "bidirectional"))
      (node (ref "U$3") (pin "10") (pinfunction "SCLR_10") (pintype "bidirectional"))
      (node (ref "U$36") (pin "P$1") (pinfunction "P$1_P$1") (pintype "bidirectional"))
      (node (ref "U$36") (pin "P$2") (pinfunction "P$2_P$2") (pintype "bidirectional"))
      (node (ref "U$4") (pin "10") (pinfunction "SCLR_10") (pintype "bidirectional"))
      (node (ref "U$5") (pin "10") (pinfunction "SCLR_10") (pintype "bidirectional"))
    )
    (net (code "83") (name "SW_BTN") (class "Default")
      (node (ref "U$12") (pin "P$1") (pinfunction "P$1_P$1") (pintype "bidirectional"))
      (node (ref "U$12") (pin "P$2") (pinfunction "P$2_P$2") (pintype "bidirectional"))
      (node (ref "U$2") (pin "P$3") (pinfunction "SW_BTN_P$3") (pintype "bidirectional"))
    )
    (net (code "84") (name "TXD") (class "Default")
      (node (ref "U$2") (pin "P$22") (pinfunction "TXD_P$22") (pintype "bidirectional"))
      (node (ref "U$34") (pin "P$1") (pinfunction "P$1_P$1") (pintype "bidirectional"))
      (node (ref "U$34") (pin "P$2") (pinfunction "P$2_P$2") (pintype "bidirectional"))
    )
    (net (code "85") (name "VDD") (class "Default")
      (node (ref "C1") (pin "1") (pinfunction "1_1") (pintype "passive"))
      (node (ref "SJ1") (pin "1") (pinfunction "1_1") (pintype "passive"))
      (node (ref "U$1") (pin "16") (pinfunction "VCC_16") (pintype "bidirectional"))
      (node (ref "U$2") (pin "P$2") (pinfunction "BAT_IN_P$2") (pintype "bidirectional"))
      (node (ref "U$3") (pin "16") (pinfunction "VCC_16") (pintype "bidirectional"))
      (node (ref "U$4") (pin "16") (pinfunction "VCC_16") (pintype "bidirectional"))
      (node (ref "U$5") (pin "16") (pinfunction "VCC_16") (pintype "bidirectional"))
    )
    (net (code "86") (name "WAKEUP") (class "Default")
      (node (ref "U$11") (pin "P$1") (pinfunction "P$1_P$1") (pintype "bidirectional"))
      (node (ref "U$11") (pin "P$2") (pinfunction "P$2_P$2") (pintype "bidirectional"))
      (node (ref "U$2") (pin "P$7") (pinfunction "WAKEUP_P$7") (pintype "bidirectional"))
    )
    (net (code "87") (name "unconnected-(RN2-PadP$3)") (class "Default")
      (node (ref "RN2") (pin "P$3") (pinfunction "P$3_P$3") (pintype "bidirectional"))
    )
    (net (code "88") (name "unconnected-(RN2-PadP$4)") (class "Default")
      (node (ref "RN2") (pin "P$4") (pinfunction "P$4_P$4") (pintype "bidirectional"))
    )
    (net (code "89") (name "unconnected-(RN2-PadP$7)") (class "Default")
      (node (ref "RN2") (pin "P$7") (pinfunction "P$7_P$7") (pintype "bidirectional"))
    )
    (net (code "90") (name "unconnected-(RN2-PadP$8)") (class "Default")
      (node (ref "RN2") (pin "P$8") (pinfunction "P$8_P$8") (pintype "bidirectional"))
    )
    (net (code "91") (name "unconnected-(SJ1-Pad2)") (class "Default")
      (node (ref "SJ1") (pin "2") (pinfunction "2_2") (pintype "passive"))
    )
    (net (code "92") (name "unconnected-(SJ2-Pad2)") (class "Default")
      (node (ref "SJ2") (pin "2") (pinfunction "2_2") (pintype "passive"))
    )
    (net (code "93") (name "unconnected-(U$1-QG-Pad6)") (class "Default")
      (node (ref "U$1") (pin "6") (pinfunction "QG_6") (pintype "bidirectional"))
    )
    (net (code "94") (name "unconnected-(U$1-QH*-Pad9)") (class "Default")
      (node (ref "U$1") (pin "9") (pinfunction "QH*_9") (pintype "bidirectional"))
    )
    (net (code "95") (name "unconnected-(U$1-QH-Pad7)") (class "Default")
      (node (ref "U$1") (pin "7") (pinfunction "QH_7") (pintype "bidirectional"))
    )
    (net (code "96") (name "unconnected-(U$2-LDO18_O-PadP$6)") (class "Default")
      (node (ref "U$2") (pin "P$6") (pinfunction "LDO18_O_P$6") (pintype "bidirectional"))
    )
    (net (code "97") (name "unconnected-(U$2-PMULDO_O-PadP$8)") (class "Default")
      (node (ref "U$2") (pin "P$8") (pinfunction "PMULDO_O_P$8") (pintype "bidirectional"))
    )
    (net (code "98") (name "unconnected-(U$3-QG-Pad6)") (class "Default")
      (node (ref "U$3") (pin "6") (pinfunction "QG_6") (pintype "bidirectional"))
    )
    (net (code "99") (name "unconnected-(U$3-QH*-Pad9)") (class "Default")
      (node (ref "U$3") (pin "9") (pinfunction "QH*_9") (pintype "bidirectional"))
    )
    (net (code "100") (name "unconnected-(U$3-QH-Pad7)") (class "Default")
      (node (ref "U$3") (pin "7") (pinfunction "QH_7") (pintype "bidirectional"))
    )
    (net (code "101") (name "unconnected-(U$4-QG-Pad6)") (class "Default")
      (node (ref "U$4") (pin "6") (pinfunction "QG_6") (pintype "bidirectional"))
    )
    (net (code "102") (name "unconnected-(U$4-QH*-Pad9)") (class "Default")
      (node (ref "U$4") (pin "9") (pinfunction "QH*_9") (pintype "bidirectional"))
    )
    (net (code "103") (name "unconnected-(U$4-QH-Pad7)") (class "Default")
      (node (ref "U$4") (pin "7") (pinfunction "QH_7") (pintype "bidirectional"))
    )
    (net (code "104") (name "unconnected-(U$5-QG-Pad6)") (class "Default")
      (node (ref "U$5") (pin "6") (pinfunction "QG_6") (pintype "bidirectional"))
    )
    (net (code "105") (name "unconnected-(U$5-QH*-Pad9)") (class "Default")
      (node (ref "U$5") (pin "9") (pinfunction "QH*_9") (pintype "bidirectional"))
    )
    (net (code "106") (name "unconnected-(U$5-QH-Pad7)") (class "Default")
      (node (ref "U$5") (pin "7") (pinfunction "QH_7") (pintype "bidirectional"))
    )
    (net (code "107") (name "unconnected-(U$40-PadP$3)") (class "Default")
      (node (ref "U$40") (pin "P$3") (pinfunction "P$3_P$3") (pintype "bidirectional"))
    )
    (net (code "108") (name "unconnected-(U$40-PadP$4)") (class "Default")
      (node (ref "U$40") (pin "P$4") (pinfunction "P$4_P$4") (pintype "bidirectional"))
    )
    (net (code "109") (name "unconnected-(U$40-PadP$7)") (class "Default")
      (node (ref "U$40") (pin "P$7") (pinfunction "P$7_P$7") (pintype "bidirectional"))
    )
    (net (code "110") (name "unconnected-(U$40-PadP$8)") (class "Default")
      (node (ref "U$40") (pin "P$8") (pinfunction "P$8_P$8") (pintype "bidirectional"))
    )
    (net (code "111") (name "unconnected-(U$42-PadP$3)") (class "Default")
      (node (ref "U$42") (pin "P$3") (pinfunction "P$3_P$3") (pintype "bidirectional"))
    )
    (net (code "112") (name "unconnected-(U$42-PadP$4)") (class "Default")
      (node (ref "U$42") (pin "P$4") (pinfunction "P$4_P$4") (pintype "bidirectional"))
    )
    (net (code "113") (name "unconnected-(U$42-PadP$7)") (class "Default")
      (node (ref "U$42") (pin "P$7") (pinfunction "P$7_P$7") (pintype "bidirectional"))
    )
    (net (code "114") (name "unconnected-(U$42-PadP$8)") (class "Default")
      (node (ref "U$42") (pin "P$8") (pinfunction "P$8_P$8") (pintype "bidirectional"))
    )
    (net (code "115") (name "unconnected-(U$44-PadP$3)") (class "Default")
      (node (ref "U$44") (pin "P$3") (pinfunction "P$3_P$3") (pintype "bidirectional"))
    )
    (net (code "116") (name "unconnected-(U$44-PadP$4)") (class "Default")
      (node (ref "U$44") (pin "P$4") (pinfunction "P$4_P$4") (pintype "bidirectional"))
    )
    (net (code "117") (name "unconnected-(U$44-PadP$7)") (class "Default")
      (node (ref "U$44") (pin "P$7") (pinfunction "P$7_P$7") (pintype "bidirectional"))
    )
    (net (code "118") (name "unconnected-(U$44-PadP$8)") (class "Default")
      (node (ref "U$44") (pin "P$8") (pinfunction "P$8_P$8") (pintype "bidirectional"))
    )
  )
)
